# Final_Schematic.net
KiCad netlist of a schematic drawn in EAGLE
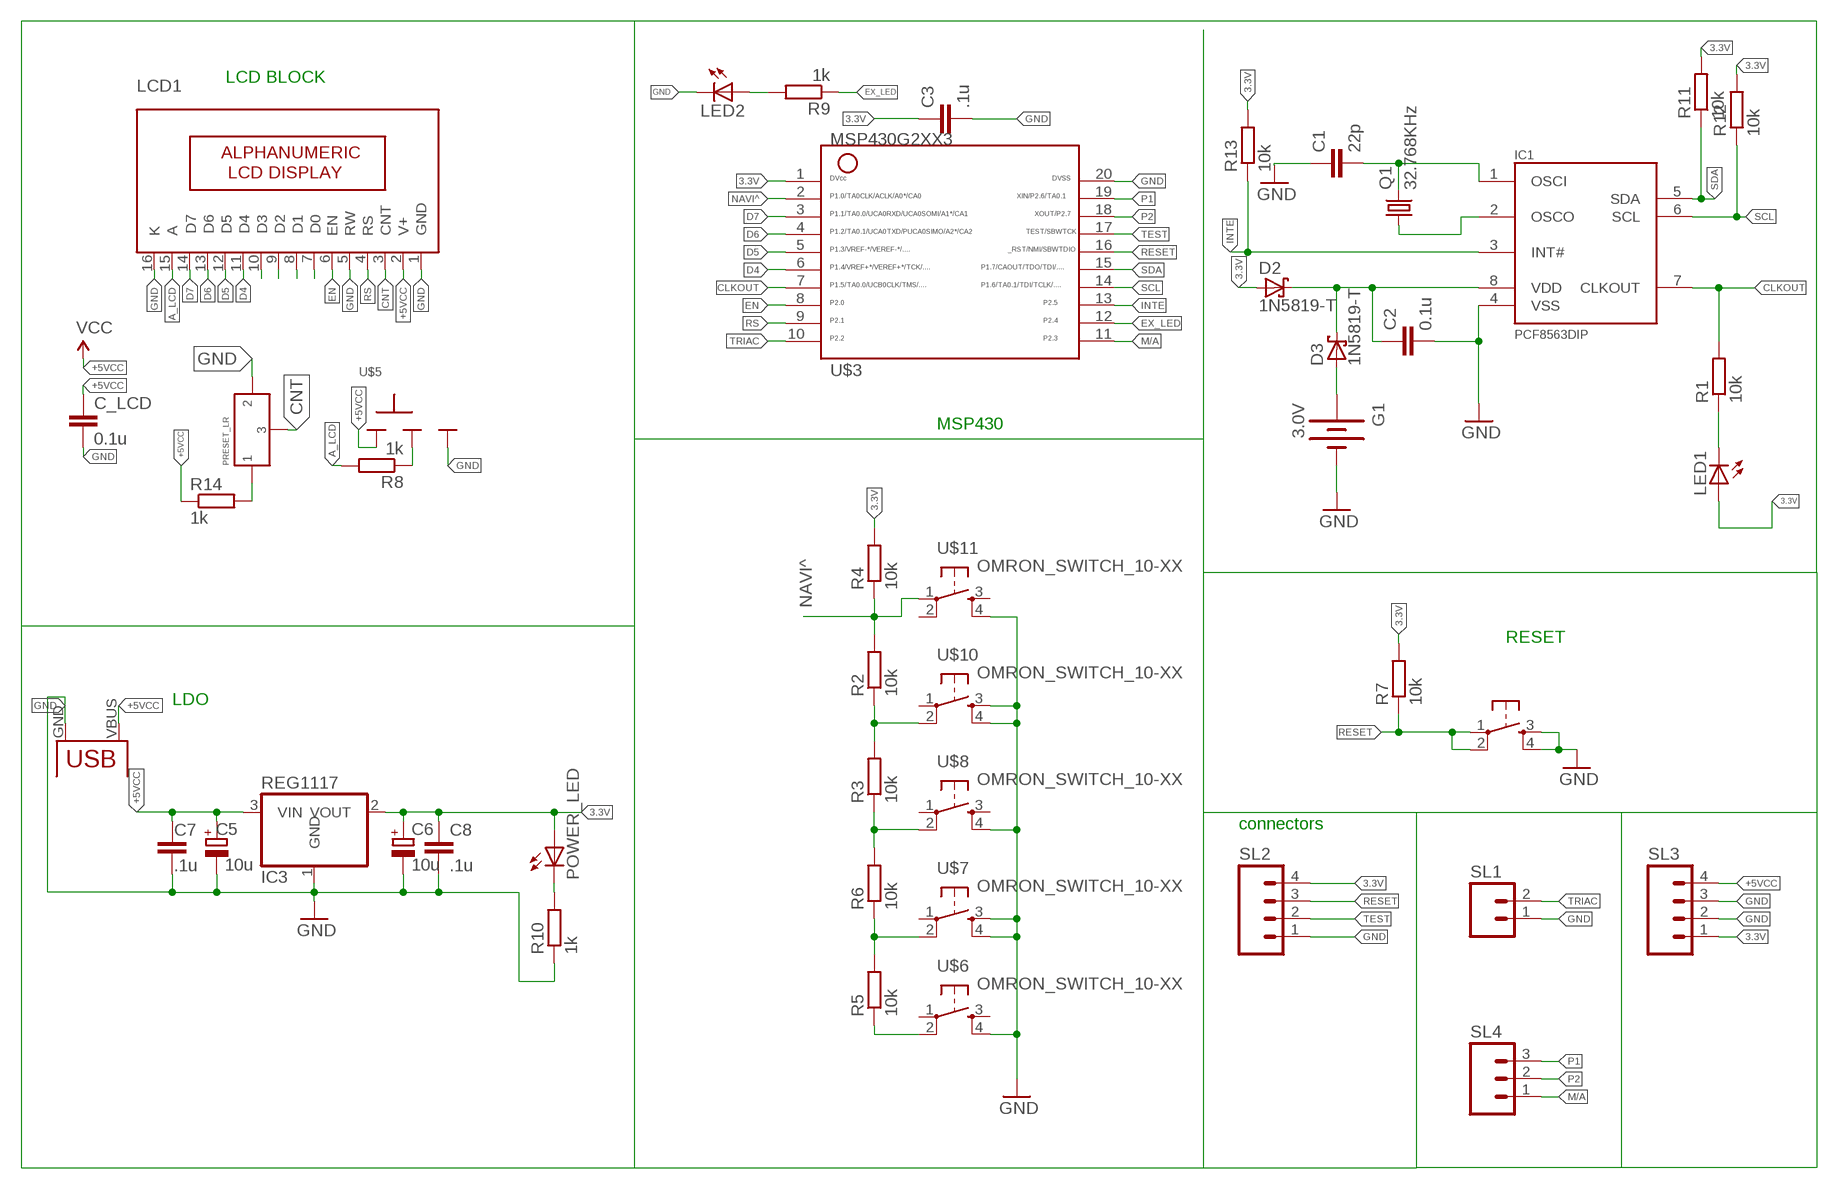
[diagram p0: schematic, sheet 1]

(export (version "E")
  (design (tool "Eeschema 10.0.6"))
  (components
    (comp (ref "C1")
      (value "22p")
      (footprint "eagle-import:C025-025X050")
      (libsource (lib "eagle-import") (part "rcl_C-EU025-025X050"))
    )
    (comp (ref "C2")
      (value "0.1u")
      (footprint "eagle-import:C025-025X050")
      (libsource (lib "eagle-import") (part "rcl_C-EU025-025X050"))
    )
    (comp (ref "C3")
      (value ".1u")
      (footprint "eagle-import:C025-025X050")
      (libsource (lib "eagle-import") (part "C-EU025-025X050"))
    )
    (comp (ref "C5")
      (value "10u")
      (footprint "eagle-import:E2,5-5")
      (libsource (lib "eagle-import") (part "CPOL-EUE2.5-5"))
    )
    (comp (ref "C6")
      (value "10u")
      (footprint "eagle-import:E2,5-5")
      (libsource (lib "eagle-import") (part "CPOL-EUE2.5-5"))
    )
    (comp (ref "C7")
      (value ".1u")
      (footprint "eagle-import:C025-025X050")
      (libsource (lib "eagle-import") (part "C-EU025-025X050"))
    )
    (comp (ref "C8")
      (value ".1u")
      (footprint "eagle-import:C025-025X050")
      (libsource (lib "eagle-import") (part "C-EU025-025X050"))
    )
    (comp (ref "C_LCD")
      (value "0.1u")
      (footprint "eagle-import:C025-025X050")
      (libsource (lib "eagle-import") (part "C-EU025-025X050"))
    )
    (comp (ref "D2")
      (value "1N5819-T")
      (footprint "eagle-import:DO41-7.6")
      (libsource (lib "eagle-import") (part "1N5819-T"))
    )
    (comp (ref "D3")
      (value "1N5819-T")
      (footprint "eagle-import:DO41-7.6")
      (libsource (lib "eagle-import") (part "1N5819-T"))
    )
    (comp (ref "G1")
      (value "3.0V")
      (footprint "eagle-import:BATTCOM_20MM_PTH")
      (libsource (lib "eagle-import") (part "BATTERY20PTH"))
    )
    (comp (ref "IC1")
      (value "PCF8563DIP")
      (footprint "eagle-import:DIL08")
      (libsource (lib "eagle-import") (part "PCF8563DIP"))
    )
    (comp (ref "IC3")
      (value "REG1117")
      (footprint "eagle-import:SOT223")
      (libsource (lib "eagle-import") (part "REG1117"))
    )
    (comp (ref "LCD1")
      (value "16X2LCD")
      (footprint "eagle-import:16X2_LCD")
      (libsource (lib "eagle-import") (part "16X2LCD"))
    )
    (comp (ref "LED1")
      (value "LED3MM")
      (footprint "eagle-import:LED3MM")
      (libsource (lib "eagle-import") (part "cpo_sdjhjasjhasjf_LED3MM"))
    )
    (comp (ref "LED2")
      (value "LED3MM")
      (footprint "eagle-import:LED3MM")
      (libsource (lib "eagle-import") (part "LED3MM"))
    )
    (comp (ref "POWER_LED")
      (value "LED3MM")
      (footprint "eagle-import:LED3MM")
      (libsource (lib "eagle-import") (part "LED3MM"))
    )
    (comp (ref "Q1")
      (value "32.768KHz")
      (footprint "eagle-import:TC26H")
      (libsource (lib "eagle-import") (part "CRYSTALTC26H"))
    )
    (comp (ref "R1")
      (value "10k")
      (footprint "eagle-import:0207_7")
      (libsource (lib "eagle-import") (part "resistor_R-EU_0207/7"))
    )
    (comp (ref "R2")
      (value "10k")
      (footprint "eagle-import:0207_7")
      (libsource (lib "eagle-import") (part "resistor_R-EU_0207/7"))
    )
    (comp (ref "R3")
      (value "10k")
      (footprint "eagle-import:0207_7")
      (libsource (lib "eagle-import") (part "resistor_R-EU_0207/7"))
    )
    (comp (ref "R4")
      (value "10k")
      (footprint "eagle-import:0207_7")
      (libsource (lib "eagle-import") (part "resistor_R-EU_0207/7"))
    )
    (comp (ref "R5")
      (value "10k")
      (footprint "eagle-import:0207_7")
      (libsource (lib "eagle-import") (part "resistor_R-EU_0207/7"))
    )
    (comp (ref "R6")
      (value "10k")
      (footprint "eagle-import:0207_7")
      (libsource (lib "eagle-import") (part "resistor_R-EU_0207/7"))
    )
    (comp (ref "R7")
      (value "10k")
      (footprint "eagle-import:0207_7")
      (libsource (lib "eagle-import") (part "resistor_R-EU_0207/7"))
    )
    (comp (ref "R8")
      (value "1k")
      (footprint "eagle-import:0207_7")
      (libsource (lib "eagle-import") (part "cpo_sdjhjasjhasjf_R-EU_0207/7"))
    )
    (comp (ref "R9")
      (value "1k")
      (footprint "eagle-import:0207_10")
      (libsource (lib "eagle-import") (part "resistor_R-EU_0207/10"))
    )
    (comp (ref "R10")
      (value "1k")
      (footprint "eagle-import:0207_7")
      (libsource (lib "eagle-import") (part "resistor_R-EU_0207/7"))
    )
    (comp (ref "R11")
      (value "10k")
      (footprint "eagle-import:0207_7")
      (libsource (lib "eagle-import") (part "resistor_R-EU_0207/7"))
    )
    (comp (ref "R12")
      (value "10k")
      (footprint "eagle-import:0207_10")
      (libsource (lib "eagle-import") (part "resistor_R-EU_0207/10"))
    )
    (comp (ref "R13")
      (value "10k")
      (footprint "eagle-import:0207_7")
      (libsource (lib "eagle-import") (part "resistor_R-EU_0207/7"))
    )
    (comp (ref "R14")
      (value "1k")
      (footprint "eagle-import:0207_7")
      (libsource (lib "eagle-import") (part "R-EU_0207/7"))
    )
    (comp (ref "SL1")
      (value "M02")
      (footprint "eagle-import:02P")
      (libsource (lib "eagle-import") (part "M02"))
    )
    (comp (ref "SL2")
      (value "M04")
      (footprint "eagle-import:04P")
      (libsource (lib "eagle-import") (part "M04"))
    )
    (comp (ref "SL3")
      (value "M04")
      (footprint "eagle-import:04P")
      (libsource (lib "eagle-import") (part "M04"))
    )
    (comp (ref "SL4")
      (value "M03")
      (footprint "eagle-import:03P")
      (libsource (lib "eagle-import") (part "M03"))
    )
    (comp (ref "U$1")
      (value "PRESET_LR")
      (footprint "eagle-import:PRESET_LR")
      (libsource (lib "eagle-import") (part "PRESET_LR"))
    )
    (comp (ref "U$2")
      (value "USB(POWER)")
      (footprint "eagle-import:USB(POWER)")
      (libsource (lib "eagle-import") (part "USB(POWER)"))
    )
    (comp (ref "U$3")
      (value "MSP430G2553DIP20")
      (footprint "eagle-import:G2553-DIP20")
      (libsource (lib "eagle-import") (part "MSP430G2553DIP20"))
    )
    (comp (ref "U$5")
      (value "SLIDESWITCH-BIG")
      (footprint "eagle-import:BIGSWITCH")
      (libsource (lib "eagle-import") (part "SLIDESWITCH-BIG"))
    )
    (comp (ref "U$6")
      (value "OMRON_SWITCH_10-XX")
      (footprint "eagle-import:B3F-10XX")
      (libsource (lib "eagle-import") (part "cpo_sdjhjasjhasjf_OMRON_SWITCH_10-XX"))
    )
    (comp (ref "U$7")
      (value "OMRON_SWITCH_10-XX")
      (footprint "eagle-import:B3F-10XX")
      (libsource (lib "eagle-import") (part "cpo_sdjhjasjhasjf_OMRON_SWITCH_10-XX"))
    )
    (comp (ref "U$8")
      (value "OMRON_SWITCH_10-XX")
      (footprint "eagle-import:B3F-10XX")
      (libsource (lib "eagle-import") (part "cpo_sdjhjasjhasjf_OMRON_SWITCH_10-XX"))
    )
    (comp (ref "U$9")
      (value "OMRON_SWITCH_10-XX")
      (footprint "eagle-import:B3F-10XX")
      (libsource (lib "eagle-import") (part "OMRON_SWITCH_10-XX"))
    )
    (comp (ref "U$10")
      (value "OMRON_SWITCH_10-XX")
      (footprint "eagle-import:B3F-10XX")
      (libsource (lib "eagle-import") (part "cpo_sdjhjasjhasjf_OMRON_SWITCH_10-XX"))
    )
    (comp (ref "U$11")
      (value "OMRON_SWITCH_10-XX")
      (footprint "eagle-import:B3F-10XX")
      (libsource (lib "eagle-import") (part "cpo_sdjhjasjhasjf_OMRON_SWITCH_10-XX"))
    )
  )
  (nets
    (net (code "1") (name "+5VCC") (class "Default")
      (node (ref "C5") (pin "+") (pinfunction "+_+") (pintype "passive"))
      (node (ref "C7") (pin "1") (pinfunction "1_1") (pintype "passive"))
      (node (ref "C_LCD") (pin "1") (pinfunction "1_1") (pintype "passive"))
      (node (ref "IC3") (pin "3") (pinfunction "VIN_3") (pintype "input"))
      (node (ref "LCD1") (pin "2") (pinfunction "V+_2") (pintype "bidirectional"))
      (node (ref "R14") (pin "1") (pinfunction "1_1") (pintype "passive"))
      (node (ref "SL3") (pin "4") (pinfunction "4_4") (pintype "passive"))
      (node (ref "U$2") (pin "VBUS") (pinfunction "VCC_VBUS") (pintype "power_in"))
      (node (ref "U$5") (pin "1") (pinfunction "1_1") (pintype "bidirectional"))
    )
    (net (code "2") (name "3.3V") (class "Default")
      (node (ref "C3") (pin "1") (pinfunction "1_1") (pintype "passive"))
      (node (ref "C6") (pin "+") (pinfunction "+_+") (pintype "passive"))
      (node (ref "C8") (pin "1") (pinfunction "1_1") (pintype "passive"))
      (node (ref "D2") (pin "A") (pinfunction "A_A") (pintype "passive"))
      (node (ref "IC3") (pin "2") (pinfunction "VOUT_2") (pintype "output"))
      (node (ref "LED1") (pin "A") (pinfunction "A_A") (pintype "passive"))
      (node (ref "POWER_LED") (pin "A") (pinfunction "A_A") (pintype "passive"))
      (node (ref "R11") (pin "2") (pinfunction "2_2") (pintype "passive"))
      (node (ref "R12") (pin "2") (pinfunction "2_2") (pintype "passive"))
      (node (ref "R13") (pin "2") (pinfunction "2_2") (pintype "passive"))
      (node (ref "R4") (pin "2") (pinfunction "2_2") (pintype "passive"))
      (node (ref "R7") (pin "2") (pinfunction "2_2") (pintype "passive"))
      (node (ref "SL2") (pin "4") (pinfunction "4_4") (pintype "passive"))
      (node (ref "SL3") (pin "1") (pinfunction "1_1") (pintype "passive"))
      (node (ref "U$3") (pin "1") (pinfunction "1_1") (pintype "power_in"))
    )
    (net (code "3") (name "A_LCD") (class "Default")
      (node (ref "LCD1") (pin "15") (pinfunction "A_15") (pintype "bidirectional"))
      (node (ref "R8") (pin "2") (pinfunction "2_2") (pintype "passive"))
    )
    (net (code "4") (name "CLKOUT") (class "Default")
      (node (ref "IC1") (pin "7") (pinfunction "CLKOUT_7") (pintype "bidirectional"))
      (node (ref "R1") (pin "2") (pinfunction "2_2") (pintype "passive"))
      (node (ref "U$3") (pin "7") (pinfunction "7_7") (pintype "bidirectional"))
    )
    (net (code "5") (name "CNT") (class "Default")
      (node (ref "LCD1") (pin "3") (pinfunction "CNT_3") (pintype "bidirectional"))
      (node (ref "U$1") (pin "P$3") (pinfunction "3_P$3") (pintype "passive"))
    )
    (net (code "6") (name "D4") (class "Default")
      (node (ref "LCD1") (pin "11") (pinfunction "D4_11") (pintype "bidirectional"))
      (node (ref "U$3") (pin "6") (pinfunction "6_6") (pintype "bidirectional"))
    )
    (net (code "7") (name "D5") (class "Default")
      (node (ref "LCD1") (pin "12") (pinfunction "D5_12") (pintype "bidirectional"))
      (node (ref "U$3") (pin "5") (pinfunction "5_5") (pintype "bidirectional"))
    )
    (net (code "8") (name "D6") (class "Default")
      (node (ref "LCD1") (pin "13") (pinfunction "D6_13") (pintype "bidirectional"))
      (node (ref "U$3") (pin "4") (pinfunction "4_4") (pintype "bidirectional"))
    )
    (net (code "9") (name "D7") (class "Default")
      (node (ref "LCD1") (pin "14") (pinfunction "D7_14") (pintype "bidirectional"))
      (node (ref "U$3") (pin "3") (pinfunction "3_3") (pintype "bidirectional"))
    )
    (net (code "10") (name "EN") (class "Default")
      (node (ref "LCD1") (pin "6") (pinfunction "EN_6") (pintype "bidirectional"))
      (node (ref "U$3") (pin "8") (pinfunction "8_8") (pintype "bidirectional"))
    )
    (net (code "11") (name "EX_LED") (class "Default")
      (node (ref "R9") (pin "1") (pinfunction "1_1") (pintype "passive"))
      (node (ref "U$3") (pin "12") (pinfunction "12_12") (pintype "bidirectional"))
    )
    (net (code "12") (name "GND") (class "Default")
      (node (ref "C1") (pin "1") (pinfunction "1_1") (pintype "passive"))
      (node (ref "C2") (pin "2") (pinfunction "2_2") (pintype "passive"))
      (node (ref "C3") (pin "2") (pinfunction "2_2") (pintype "passive"))
      (node (ref "C5") (pin "-") (pinfunction "-_-") (pintype "passive"))
      (node (ref "C6") (pin "-") (pinfunction "-_-") (pintype "passive"))
      (node (ref "C7") (pin "2") (pinfunction "2_2") (pintype "passive"))
      (node (ref "C8") (pin "2") (pinfunction "2_2") (pintype "passive"))
      (node (ref "C_LCD") (pin "2") (pinfunction "2_2") (pintype "passive"))
      (node (ref "G1") (pin "2") (pinfunction "-_2") (pintype "power_in"))
      (node (ref "IC1") (pin "4") (pinfunction "VSS_4") (pintype "bidirectional"))
      (node (ref "IC3") (pin "1") (pinfunction "GND_1") (pintype "power_in"))
      (node (ref "LCD1") (pin "1") (pinfunction "GND_1") (pintype "bidirectional"))
      (node (ref "LCD1") (pin "16") (pinfunction "K_16") (pintype "bidirectional"))
      (node (ref "LCD1") (pin "5") (pinfunction "RW_5") (pintype "bidirectional"))
      (node (ref "LED2") (pin "K") (pinfunction "C_K") (pintype "passive"))
      (node (ref "R10") (pin "1") (pinfunction "1_1") (pintype "passive"))
      (node (ref "SL1") (pin "1") (pinfunction "1_1") (pintype "passive"))
      (node (ref "SL2") (pin "1") (pinfunction "1_1") (pintype "passive"))
      (node (ref "SL3") (pin "2") (pinfunction "2_2") (pintype "passive"))
      (node (ref "SL3") (pin "3") (pinfunction "3_3") (pintype "passive"))
      (node (ref "U$1") (pin "P$2") (pinfunction "2_P$2") (pintype "passive"))
      (node (ref "U$10") (pin "3") (pinfunction "S_3") (pintype "passive"))
      (node (ref "U$10") (pin "4") (pinfunction "S1_4") (pintype "passive"))
      (node (ref "U$11") (pin "4") (pinfunction "S1_4") (pintype "passive"))
      (node (ref "U$2") (pin "GND") (pinfunction "GND_GND") (pintype "power_in"))
      (node (ref "U$3") (pin "20") (pinfunction "20_20") (pintype "power_in"))
      (node (ref "U$5") (pin "3") (pinfunction "3_3") (pintype "bidirectional"))
      (node (ref "U$6") (pin "4") (pinfunction "S1_4") (pintype "passive"))
      (node (ref "U$7") (pin "3") (pinfunction "S_3") (pintype "passive"))
      (node (ref "U$7") (pin "4") (pinfunction "S1_4") (pintype "passive"))
      (node (ref "U$8") (pin "4") (pinfunction "S1_4") (pintype "passive"))
      (node (ref "U$9") (pin "3") (pinfunction "S_3") (pintype "passive"))
      (node (ref "U$9") (pin "4") (pinfunction "S1_4") (pintype "passive"))
    )
    (net (code "13") (name "INTE") (class "Default")
      (node (ref "IC1") (pin "3") (pinfunction "INT#_3") (pintype "bidirectional"))
      (node (ref "R13") (pin "1") (pinfunction "1_1") (pintype "passive"))
      (node (ref "U$3") (pin "13") (pinfunction "13_13") (pintype "bidirectional"))
    )
    (net (code "14") (name "M{slash}A") (class "Default")
      (node (ref "SL4") (pin "1") (pinfunction "1_1") (pintype "passive"))
      (node (ref "U$3") (pin "11") (pinfunction "11_11") (pintype "bidirectional"))
    )
    (net (code "15") (name "NAVI^") (class "Default")
      (node (ref "R2") (pin "2") (pinfunction "2_2") (pintype "passive"))
      (node (ref "R4") (pin "1") (pinfunction "1_1") (pintype "passive"))
      (node (ref "U$11") (pin "1") (pinfunction "P_1") (pintype "passive"))
      (node (ref "U$3") (pin "2") (pinfunction "2_2") (pintype "bidirectional"))
    )
    (net (code "16") (name "Net-(G1-+)") (class "Default")
      (node (ref "D3") (pin "A") (pinfunction "A_A") (pintype "passive"))
      (node (ref "G1") (pin "1") (pinfunction "+_1") (pintype "power_in"))
    )
    (net (code "17") (name "Net-(IC1-OSCI)") (class "Default")
      (node (ref "C1") (pin "2") (pinfunction "2_2") (pintype "passive"))
      (node (ref "IC1") (pin "1") (pinfunction "OSCI_1") (pintype "bidirectional"))
      (node (ref "Q1") (pin "2") (pinfunction "2_2") (pintype "passive"))
    )
    (net (code "18") (name "Net-(IC1-OSCO)") (class "Default")
      (node (ref "IC1") (pin "2") (pinfunction "OSCO_2") (pintype "bidirectional"))
      (node (ref "Q1") (pin "1") (pinfunction "1_1") (pintype "passive"))
    )
    (net (code "19") (name "Net-(IC1-VDD)") (class "Default")
      (node (ref "C2") (pin "1") (pinfunction "1_1") (pintype "passive"))
      (node (ref "D2") (pin "C") (pinfunction "C_C") (pintype "passive"))
      (node (ref "D3") (pin "C") (pinfunction "C_C") (pintype "passive"))
      (node (ref "IC1") (pin "8") (pinfunction "VDD_8") (pintype "bidirectional"))
    )
    (net (code "20") (name "Net-(LED1-C)") (class "Default")
      (node (ref "LED1") (pin "K") (pinfunction "C_K") (pintype "passive"))
      (node (ref "R1") (pin "1") (pinfunction "1_1") (pintype "passive"))
    )
    (net (code "21") (name "Net-(LED2-PadA)") (class "Default")
      (node (ref "LED2") (pin "A") (pinfunction "A_A") (pintype "passive"))
      (node (ref "R9") (pin "2") (pinfunction "2_2") (pintype "passive"))
    )
    (net (code "22") (name "Net-(POWER_LED-C)") (class "Default")
      (node (ref "POWER_LED") (pin "K") (pinfunction "C_K") (pintype "passive"))
      (node (ref "R10") (pin "2") (pinfunction "2_2") (pintype "passive"))
    )
    (net (code "23") (name "Net-(R8-Pad1)") (class "Default")
      (node (ref "R8") (pin "1") (pinfunction "1_1") (pintype "passive"))
      (node (ref "U$5") (pin "2") (pinfunction "2_2") (pintype "bidirectional"))
    )
    (net (code "24") (name "Net-(U$1-1)") (class "Default")
      (node (ref "R14") (pin "2") (pinfunction "2_2") (pintype "passive"))
      (node (ref "U$1") (pin "P$1") (pinfunction "1_P$1") (pintype "passive"))
    )
    (net (code "25") (name "Net-(U$6-P1)") (class "Default")
      (node (ref "R5") (pin "1") (pinfunction "1_1") (pintype "passive"))
      (node (ref "U$6") (pin "2") (pinfunction "P1_2") (pintype "passive"))
    )
    (net (code "26") (name "Net-(U$7-P1)") (class "Default")
      (node (ref "R5") (pin "2") (pinfunction "2_2") (pintype "passive"))
      (node (ref "R6") (pin "1") (pinfunction "1_1") (pintype "passive"))
      (node (ref "U$7") (pin "2") (pinfunction "P1_2") (pintype "passive"))
    )
    (net (code "27") (name "Net-(U$8-P1)") (class "Default")
      (node (ref "R3") (pin "1") (pinfunction "1_1") (pintype "passive"))
      (node (ref "R6") (pin "2") (pinfunction "2_2") (pintype "passive"))
      (node (ref "U$8") (pin "2") (pinfunction "P1_2") (pintype "passive"))
    )
    (net (code "28") (name "Net-(U$10-P1)") (class "Default")
      (node (ref "R2") (pin "1") (pinfunction "1_1") (pintype "passive"))
      (node (ref "R3") (pin "2") (pinfunction "2_2") (pintype "passive"))
      (node (ref "U$10") (pin "2") (pinfunction "P1_2") (pintype "passive"))
    )
    (net (code "29") (name "P1") (class "Default")
      (node (ref "SL4") (pin "3") (pinfunction "3_3") (pintype "passive"))
      (node (ref "U$3") (pin "19") (pinfunction "19_19") (pintype "bidirectional"))
    )
    (net (code "30") (name "P2") (class "Default")
      (node (ref "SL4") (pin "2") (pinfunction "2_2") (pintype "passive"))
      (node (ref "U$3") (pin "18") (pinfunction "18_18") (pintype "bidirectional"))
    )
    (net (code "31") (name "RESET") (class "Default")
      (node (ref "R7") (pin "1") (pinfunction "1_1") (pintype "passive"))
      (node (ref "SL2") (pin "3") (pinfunction "3_3") (pintype "passive"))
      (node (ref "U$3") (pin "16") (pinfunction "16_16") (pintype "bidirectional"))
      (node (ref "U$9") (pin "1") (pinfunction "P_1") (pintype "passive"))
      (node (ref "U$9") (pin "2") (pinfunction "P1_2") (pintype "passive"))
    )
    (net (code "32") (name "RS") (class "Default")
      (node (ref "LCD1") (pin "4") (pinfunction "RS_4") (pintype "bidirectional"))
      (node (ref "U$3") (pin "9") (pinfunction "9_9") (pintype "bidirectional"))
    )
    (net (code "33") (name "SCL") (class "Default")
      (node (ref "IC1") (pin "6") (pinfunction "SCL_6") (pintype "bidirectional"))
      (node (ref "R12") (pin "1") (pinfunction "1_1") (pintype "passive"))
      (node (ref "U$3") (pin "14") (pinfunction "14_14") (pintype "bidirectional"))
    )
    (net (code "34") (name "SDA") (class "Default")
      (node (ref "IC1") (pin "5") (pinfunction "SDA_5") (pintype "bidirectional"))
      (node (ref "R11") (pin "1") (pinfunction "1_1") (pintype "passive"))
      (node (ref "U$3") (pin "15") (pinfunction "15_15") (pintype "bidirectional"))
    )
    (net (code "35") (name "TEST") (class "Default")
      (node (ref "SL2") (pin "2") (pinfunction "2_2") (pintype "passive"))
      (node (ref "U$3") (pin "17") (pinfunction "17_17") (pintype "bidirectional"))
    )
    (net (code "36") (name "TRIAC") (class "Default")
      (node (ref "SL1") (pin "2") (pinfunction "2_2") (pintype "passive"))
      (node (ref "U$3") (pin "10") (pinfunction "10_10") (pintype "bidirectional"))
    )
    (net (code "37") (name "unconnected-(LCD1-D0-Pad7)") (class "Default")
      (node (ref "LCD1") (pin "7") (pinfunction "D0_7") (pintype "bidirectional"))
    )
    (net (code "38") (name "unconnected-(LCD1-D1-Pad8)") (class "Default")
      (node (ref "LCD1") (pin "8") (pinfunction "D1_8") (pintype "bidirectional"))
    )
    (net (code "39") (name "unconnected-(LCD1-D2-Pad9)") (class "Default")
      (node (ref "LCD1") (pin "9") (pinfunction "D2_9") (pintype "bidirectional"))
    )
    (net (code "40") (name "unconnected-(LCD1-D3-Pad10)") (class "Default")
      (node (ref "LCD1") (pin "10") (pinfunction "D3_10") (pintype "bidirectional"))
    )
    (net (code "41") (name "unconnected-(U$6-P-Pad1)") (class "Default")
      (node (ref "U$6") (pin "1") (pinfunction "P_1") (pintype "passive"))
    )
    (net (code "42") (name "unconnected-(U$6-S-Pad3)") (class "Default")
      (node (ref "U$6") (pin "3") (pinfunction "S_3") (pintype "passive"))
    )
    (net (code "43") (name "unconnected-(U$7-P-Pad1)") (class "Default")
      (node (ref "U$7") (pin "1") (pinfunction "P_1") (pintype "passive"))
    )
    (net (code "44") (name "unconnected-(U$8-P-Pad1)") (class "Default")
      (node (ref "U$8") (pin "1") (pinfunction "P_1") (pintype "passive"))
    )
    (net (code "45") (name "unconnected-(U$8-S-Pad3)") (class "Default")
      (node (ref "U$8") (pin "3") (pinfunction "S_3") (pintype "passive"))
    )
    (net (code "46") (name "unconnected-(U$10-P-Pad1)") (class "Default")
      (node (ref "U$10") (pin "1") (pinfunction "P_1") (pintype "passive"))
    )
    (net (code "47") (name "unconnected-(U$11-P1-Pad2)") (class "Default")
      (node (ref "U$11") (pin "2") (pinfunction "P1_2") (pintype "passive"))
    )
    (net (code "48") (name "unconnected-(U$11-S-Pad3)") (class "Default")
      (node (ref "U$11") (pin "3") (pinfunction "S_3") (pintype "passive"))
    )
  )
)
